# Tiny_Programmer_PB.net
KiCad netlist of a schematic drawn in EAGLE
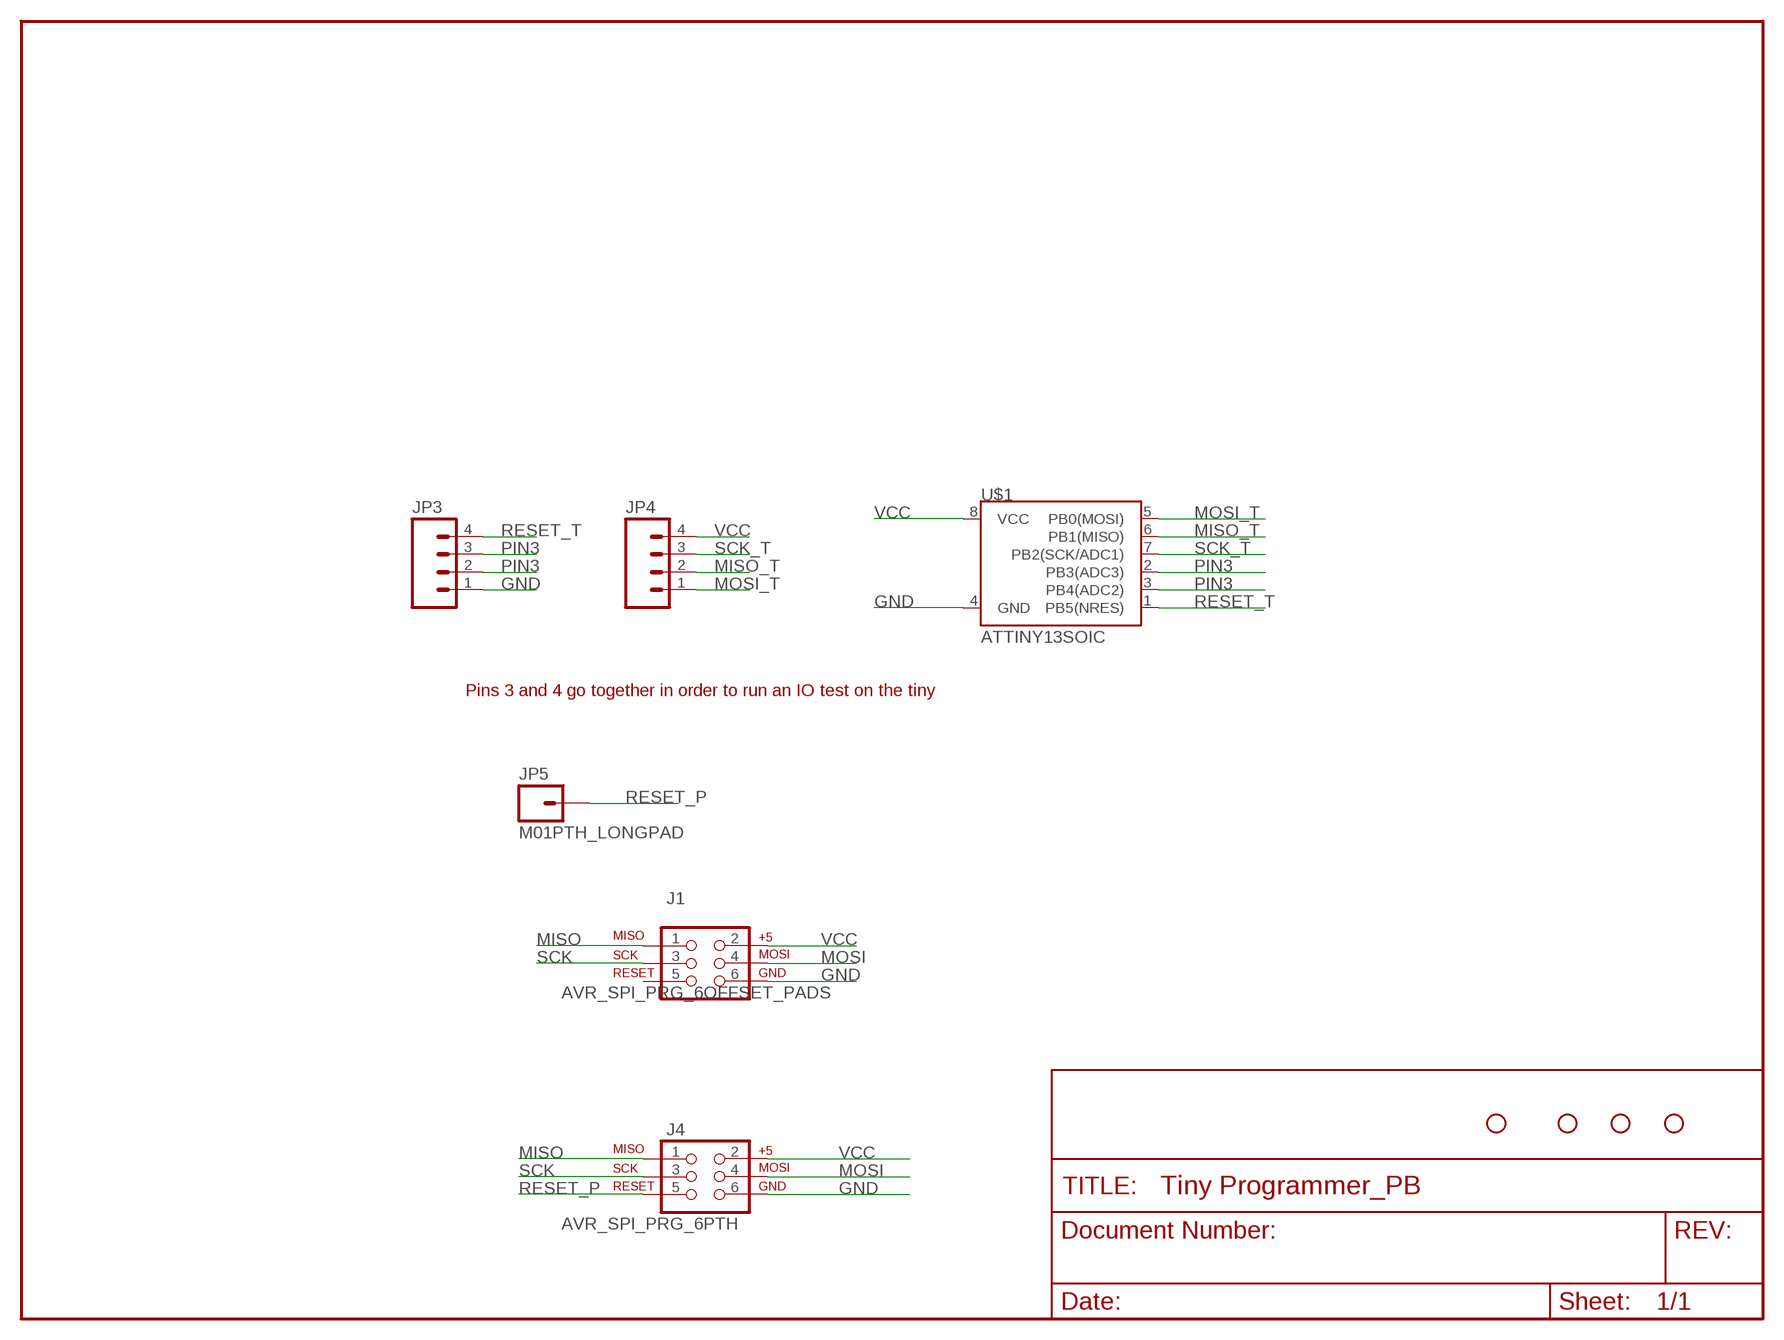
[diagram p0: schematic, sheet 1]

(export (version "E")
  (design (tool "Eeschema 10.0.6"))
  (components
    (comp (ref "J1")
      (value "AVR_SPI_PRG_6OFFSET_PADS")
      (footprint "eagle-import:2X3_OFFSET")
      (libsource (lib "eagle-import") (part "AVR_SPI_PRG_6OFFSET_PADS"))
    )
    (comp (ref "J4")
      (value "AVR_SPI_PRG_6PTH")
      (footprint "eagle-import:2X3")
      (libsource (lib "eagle-import") (part "AVR_SPI_PRG_6PTH"))
    )
    (comp (ref "JP1")
      (value "STAND-OFFTIGHTER")
      (footprint "eagle-import:STAND-OFF-TIGHTER")
      (libsource (lib "eagle-import") (part "STAND-OFFTIGHTER"))
    )
    (comp (ref "JP2")
      (value "STAND-OFFTIGHTER")
      (footprint "eagle-import:STAND-OFF-TIGHTER")
      (libsource (lib "eagle-import") (part "STAND-OFFTIGHTER"))
    )
    (comp (ref "JP3")
      (value "M04LONGPADS")
      (footprint "eagle-import:1X04_LONGPADS")
      (libsource (lib "eagle-import") (part "M04LONGPADS"))
    )
    (comp (ref "JP4")
      (value "M04LONGPADS")
      (footprint "eagle-import:1X04_LONGPADS")
      (libsource (lib "eagle-import") (part "M04LONGPADS"))
    )
    (comp (ref "JP5")
      (value "M01PTH_LONGPAD")
      (footprint "eagle-import:1X01_LONGPAD")
      (libsource (lib "eagle-import") (part "M01PTH_LONGPAD"))
    )
    (comp (ref "JP8")
      (value "STAND-OFFTIGHTER")
      (footprint "eagle-import:STAND-OFF-TIGHTER")
      (libsource (lib "eagle-import") (part "STAND-OFFTIGHTER"))
    )
    (comp (ref "JP9")
      (value "STAND-OFFTIGHTER")
      (footprint "eagle-import:STAND-OFF-TIGHTER")
      (libsource (lib "eagle-import") (part "STAND-OFFTIGHTER"))
    )
    (comp (ref "U$1")
      (value "ATTINY13SOIC")
      (footprint "eagle-import:SO08")
      (libsource (lib "eagle-import") (part "ATTINY13SOIC"))
    )
  )
  (nets
    (net (code "1") (name "/GND") (class "Default")
      (node (ref "J1") (pin "6") (pinfunction "6_6") (pintype "passive"))
      (node (ref "J4") (pin "6") (pinfunction "6_6") (pintype "passive"))
      (node (ref "JP3") (pin "1") (pinfunction "1_1") (pintype "passive"))
      (node (ref "U$1") (pin "4") (pinfunction "GND_4") (pintype "bidirectional"))
    )
    (net (code "2") (name "/MISO") (class "Default")
      (node (ref "J1") (pin "1") (pinfunction "1_1") (pintype "passive"))
      (node (ref "J4") (pin "1") (pinfunction "1_1") (pintype "passive"))
    )
    (net (code "3") (name "/MISO_T") (class "Default")
      (node (ref "JP4") (pin "2") (pinfunction "2_2") (pintype "passive"))
      (node (ref "U$1") (pin "6") (pinfunction "PB1(MISO)_6") (pintype "bidirectional"))
    )
    (net (code "4") (name "/MOSI") (class "Default")
      (node (ref "J1") (pin "4") (pinfunction "4_4") (pintype "passive"))
      (node (ref "J4") (pin "4") (pinfunction "4_4") (pintype "passive"))
    )
    (net (code "5") (name "/MOSI_T") (class "Default")
      (node (ref "JP4") (pin "1") (pinfunction "1_1") (pintype "passive"))
      (node (ref "U$1") (pin "5") (pinfunction "PB0(MOSI)_5") (pintype "bidirectional"))
    )
    (net (code "6") (name "/PIN3") (class "Default")
      (node (ref "JP3") (pin "2") (pinfunction "2_2") (pintype "passive"))
      (node (ref "JP3") (pin "3") (pinfunction "3_3") (pintype "passive"))
      (node (ref "U$1") (pin "2") (pinfunction "PB3(ADC3)_2") (pintype "bidirectional"))
      (node (ref "U$1") (pin "3") (pinfunction "PB4(ADC2)_3") (pintype "bidirectional"))
    )
    (net (code "7") (name "/RESET_P") (class "Default")
      (node (ref "J4") (pin "5") (pinfunction "5_5") (pintype "passive"))
      (node (ref "JP5") (pin "1") (pinfunction "1_1") (pintype "passive"))
    )
    (net (code "8") (name "/RESET_T") (class "Default")
      (node (ref "JP3") (pin "4") (pinfunction "4_4") (pintype "passive"))
      (node (ref "U$1") (pin "1") (pinfunction "PB5(NRES)_1") (pintype "bidirectional"))
    )
    (net (code "9") (name "/SCK") (class "Default")
      (node (ref "J1") (pin "3") (pinfunction "3_3") (pintype "passive"))
      (node (ref "J4") (pin "3") (pinfunction "3_3") (pintype "passive"))
    )
    (net (code "10") (name "/SCK_T") (class "Default")
      (node (ref "JP4") (pin "3") (pinfunction "3_3") (pintype "passive"))
      (node (ref "U$1") (pin "7") (pinfunction "PB2(SCK/ADC1)_7") (pintype "bidirectional"))
    )
    (net (code "11") (name "/VCC") (class "Default")
      (node (ref "J1") (pin "2") (pinfunction "2_2") (pintype "passive"))
      (node (ref "J4") (pin "2") (pinfunction "2_2") (pintype "passive"))
      (node (ref "JP4") (pin "4") (pinfunction "4_4") (pintype "passive"))
      (node (ref "U$1") (pin "8") (pinfunction "VCC_8") (pintype "bidirectional"))
    )
    (net (code "12") (name "unconnected-(J1-Pad5)") (class "Default")
      (node (ref "J1") (pin "5") (pinfunction "5_5") (pintype "passive"))
    )
  )
)
